# Sheet1.net
KiCad netlist of a schematic drawn in Altium Designer
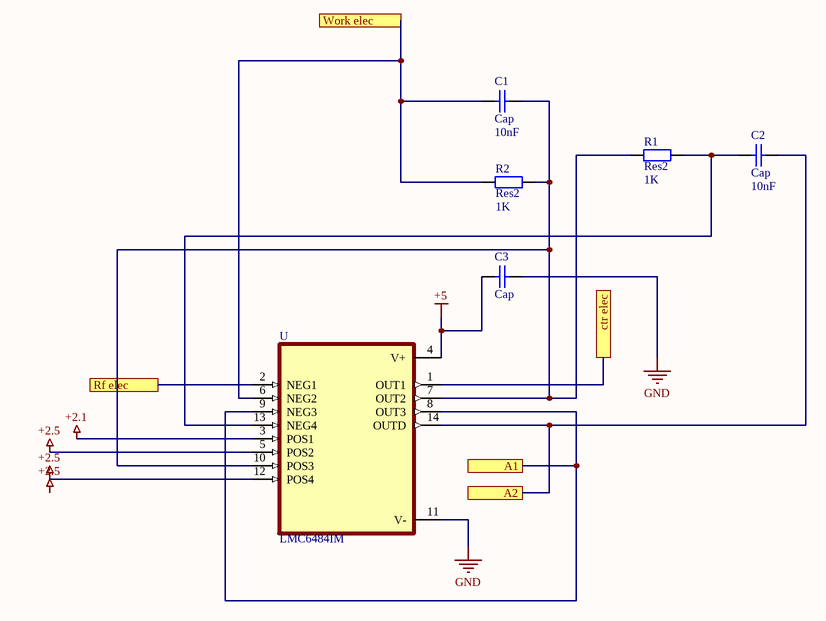
[diagram p0: Sheet1.SchDoc]

(export (version "E")
  (design (tool "Eeschema 10.0.6"))
  (components
    (comp (ref "C1")
      (value "Cap")
      (footprint "RAD-0.3")
      (description "Capacitor")
      (fields (field (name "ALTIUM_VALUE") "10nF") (field (name "PUBLISHER") "Altium Limited"))
      (libsource (lib "Miscellaneous Devices") (part "Cap"))
    )
    (comp (ref "C2")
      (value "Cap")
      (footprint "RAD-0.3")
      (description "Capacitor")
      (fields (field (name "ALTIUM_VALUE") "10nF") (field (name "PUBLISHER") "Altium Limited"))
      (libsource (lib "Miscellaneous Devices") (part "Cap"))
    )
    (comp (ref "C3")
      (value "Cap")
      (footprint "RAD-0.3")
      (description "Capacitor")
      (fields (field (name "PUBLISHER") "Altium Limited"))
      (libsource (lib "Miscellaneous Devices") (part "Cap"))
    )
    (comp (ref "R1")
      (value "Res2")
      (footprint "AXIAL-0.4")
      (description "Resistor")
      (fields (field (name "ALTIUM_VALUE") "1K") (field (name "PUBLISHER") "Altium Limited"))
      (libsource (lib "Miscellaneous Devices") (part "Res2"))
    )
    (comp (ref "R2")
      (value "Res2")
      (footprint "AXIAL-0.4")
      (description "Resistor")
      (fields (field (name "ALTIUM_VALUE") "1K") (field (name "PUBLISHER") "Altium Limited"))
      (libsource (lib "Miscellaneous Devices") (part "Res2"))
    )
    (comp (ref "U")
      (value "LMC6484IM")
      (footprint "SOIC127P600X175-14N")
      (fields (field (name "MF") "Texas Instruments") (field (name "MP") "LMC6484IM/NOPB"))
      (libsource (lib "LMC6484IM") (part "LMC6484IM"))
    )
  )
  (nets
    (net (code "1") (name "+2.1") (class "Default")
      (node (ref "U") (pin "3") (pinfunction "POS1_3") (pintype "input"))
    )
    (net (code "2") (name "+2.5") (class "Default")
      (node (ref "U") (pin "12") (pinfunction "POS4_12") (pintype "input"))
      (node (ref "U") (pin "5") (pinfunction "POS2_5") (pintype "input"))
    )
    (net (code "3") (name "+5") (class "Default")
      (node (ref "C3") (pin "1") (pinfunction "1_1") (pintype "passive"))
      (node (ref "U") (pin "4") (pinfunction "V+_4") (pintype "power_in"))
    )
    (net (code "4") (name "/ A1") (class "Default")
      (node (ref "U") (pin "8") (pinfunction "OUT3_8") (pintype "output"))
      (node (ref "U") (pin "9") (pinfunction "NEG3_9") (pintype "input"))
    )
    (net (code "5") (name "/A2") (class "Default")
      (node (ref "C2") (pin "2") (pinfunction "2_2") (pintype "passive"))
      (node (ref "U") (pin "14") (pinfunction "OUTD_14") (pintype "output"))
    )
    (net (code "6") (name "/Rf elec") (class "Default")
      (node (ref "U") (pin "2") (pinfunction "NEG1_2") (pintype "input"))
    )
    (net (code "7") (name "/Work elec") (class "Default")
      (node (ref "C1") (pin "1") (pinfunction "1_1") (pintype "passive"))
      (node (ref "R2") (pin "1") (pinfunction "1_1") (pintype "passive"))
      (node (ref "U") (pin "6") (pinfunction "NEG2_6") (pintype "input"))
    )
    (net (code "8") (name "/ctr elec") (class "Default")
      (node (ref "U") (pin "1") (pinfunction "OUT1_1") (pintype "output"))
    )
    (net (code "9") (name "GND") (class "Default")
      (node (ref "C3") (pin "2") (pinfunction "2_2") (pintype "passive"))
      (node (ref "U") (pin "11") (pinfunction "V-_11") (pintype "power_in"))
    )
    (net (code "10") (name "Net-(U-NEG4)") (class "Default")
      (node (ref "C2") (pin "1") (pinfunction "1_1") (pintype "passive"))
      (node (ref "R1") (pin "2") (pinfunction "2_2") (pintype "passive"))
      (node (ref "U") (pin "13") (pinfunction "NEG4_13") (pintype "input"))
    )
    (net (code "11") (name "Net-(U-OUT2)") (class "Default")
      (node (ref "C1") (pin "2") (pinfunction "2_2") (pintype "passive"))
      (node (ref "R1") (pin "1") (pinfunction "1_1") (pintype "passive"))
      (node (ref "R2") (pin "2") (pinfunction "2_2") (pintype "passive"))
      (node (ref "U") (pin "10") (pinfunction "POS3_10") (pintype "input"))
      (node (ref "U") (pin "7") (pinfunction "OUT2_7") (pintype "output"))
    )
  )
)
